# Czujnik_wiat_owodowy_schemat_elektryczny.net
KiCad netlist of a schematic drawn in Altium Designer
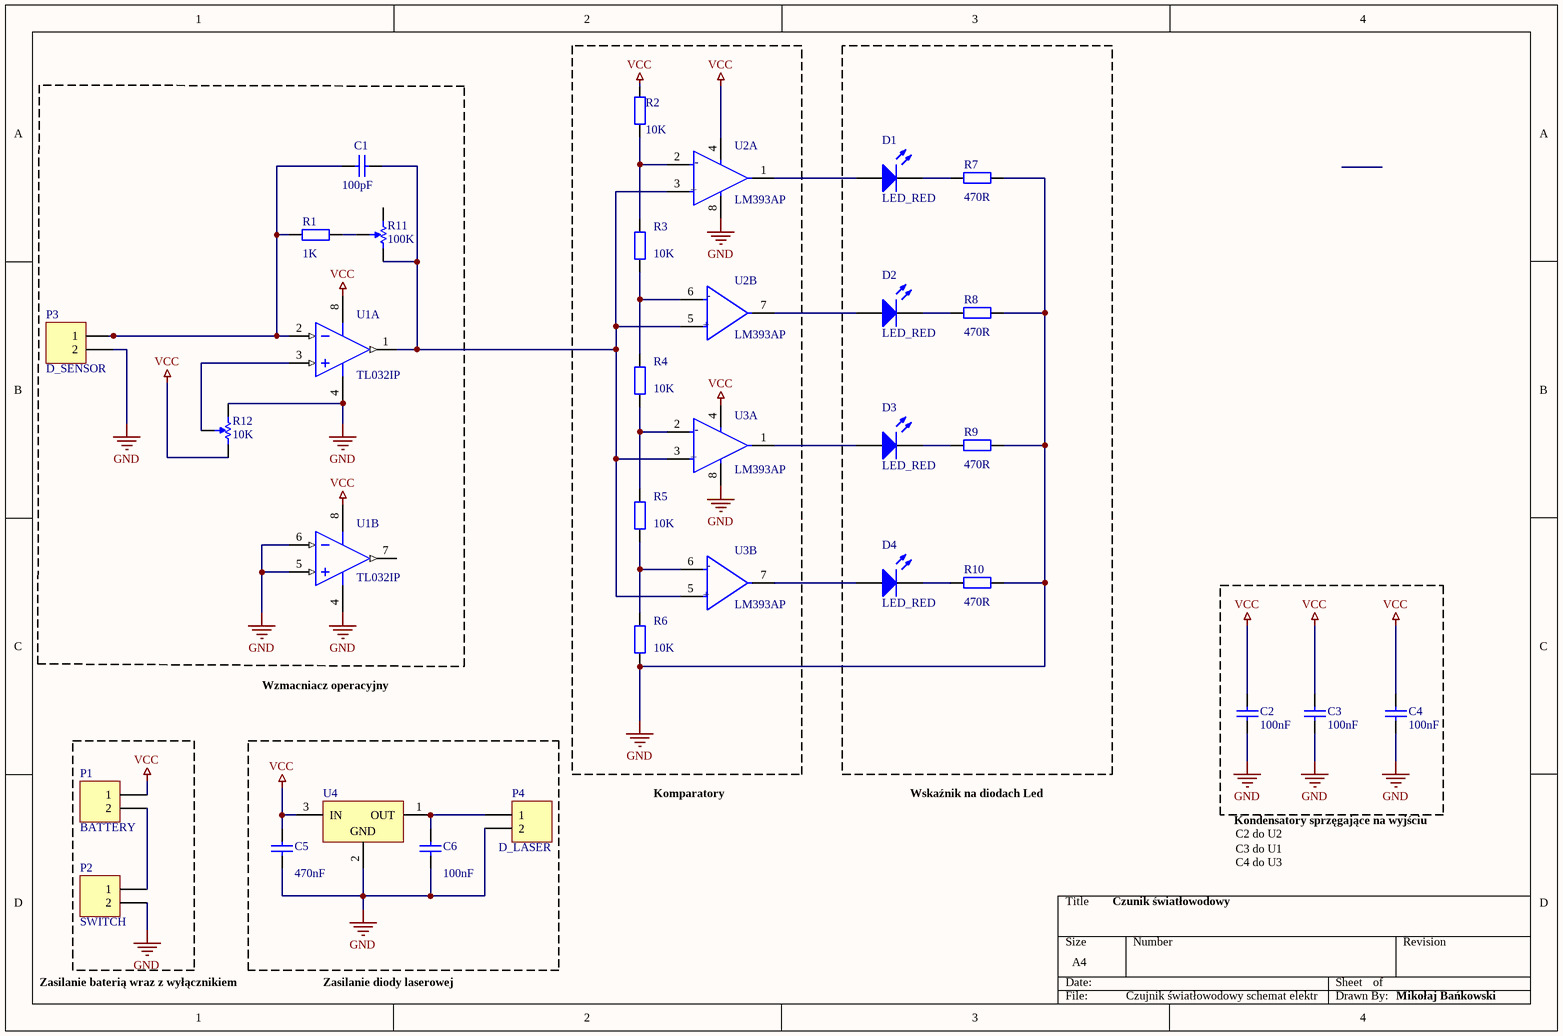
[diagram p0: Czujnik światłowodowy schemat elektryczny.SchDoc]

(export (version "E")
  (design (tool "Eeschema 10.0.6"))
  (components
    (comp (ref "C1")
      (value "100pF")
      (footprint "RAD-0.3")
      (description "Capacitor")
      (fields (field (name "Comment") "Cap") (field (name "PUBLISHER") "Altium Limited"))
      (libsource (lib "Miscellaneous Devices") (part "Cap"))
    )
    (comp (ref "C2")
      (value "100nF")
      (footprint "RAD-0.3")
      (description "Capacitor")
      (fields (field (name "Comment") "Cap") (field (name "PUBLISHER") "Altium Limited"))
      (libsource (lib "Miscellaneous Devices") (part "Cap"))
    )
    (comp (ref "C3")
      (value "100nF")
      (footprint "RAD-0.3")
      (description "Capacitor")
      (fields (field (name "Comment") "Cap") (field (name "PUBLISHER") "Altium Limited"))
      (libsource (lib "Miscellaneous Devices") (part "Cap"))
    )
    (comp (ref "C4")
      (value "100nF")
      (footprint "RAD-0.3")
      (description "Capacitor")
      (fields (field (name "Comment") "Cap") (field (name "PUBLISHER") "Altium Limited"))
      (libsource (lib "Miscellaneous Devices") (part "Cap"))
    )
    (comp (ref "C5")
      (value "470nF")
      (footprint "RAD-0.3")
      (description "Capacitor")
      (fields (field (name "Comment") "Cap") (field (name "PUBLISHER") "Altium Limited"))
      (libsource (lib "Miscellaneous Devices") (part "Cap"))
    )
    (comp (ref "C6")
      (value "100nF")
      (footprint "RAD-0.3")
      (description "Capacitor")
      (fields (field (name "Comment") "Cap") (field (name "PUBLISHER") "Altium Limited"))
      (libsource (lib "Miscellaneous Devices") (part "Cap"))
    )
    (comp (ref "D1")
      (value "LED_RED")
      (footprint "LED-1")
      (description "Typical RED GaAs LED")
      (fields (field (name "PUBLISHER") "Altium Limited"))
      (libsource (lib "Miscellaneous Devices") (part "LED1"))
    )
    (comp (ref "D2")
      (value "LED_RED")
      (footprint "LED-1")
      (description "Typical RED GaAs LED")
      (fields (field (name "PUBLISHER") "Altium Limited"))
      (libsource (lib "Miscellaneous Devices") (part "LED1"))
    )
    (comp (ref "D3")
      (value "LED_RED")
      (footprint "LED-1")
      (description "Typical RED GaAs LED")
      (fields (field (name "PUBLISHER") "Altium Limited"))
      (libsource (lib "Miscellaneous Devices") (part "LED1"))
    )
    (comp (ref "D4")
      (value "LED_RED")
      (footprint "LED-1")
      (description "Typical RED GaAs LED")
      (fields (field (name "PUBLISHER") "Altium Limited"))
      (libsource (lib "Miscellaneous Devices") (part "LED1"))
    )
    (comp (ref "P1")
      (value "BATTERY")
      (footprint "HDR1X2")
      (description "Header, 2-Pin")
      (fields (field (name "PUBLISHER") "Altium Limited"))
      (libsource (lib "Miscellaneous Connectors") (part "Header 2"))
    )
    (comp (ref "P2")
      (value "SWITCH")
      (footprint "HDR1X2")
      (description "Header, 2-Pin")
      (fields (field (name "PUBLISHER") "Altium Limited"))
      (libsource (lib "Miscellaneous Connectors") (part "Header 2"))
    )
    (comp (ref "P3")
      (value "D_SENSOR")
      (footprint "HDR1X2")
      (description "Header, 2-Pin")
      (fields (field (name "PUBLISHER") "Altium Limited"))
      (libsource (lib "Miscellaneous Connectors") (part "Header 2"))
    )
    (comp (ref "P4")
      (value "D_LASER")
      (footprint "HDR1X2")
      (description "Header, 2-Pin")
      (fields (field (name "PUBLISHER") "Altium Limited"))
      (libsource (lib "") (part "Header 2_1"))
    )
    (comp (ref "R1")
      (value "1K")
      (footprint "AXIAL-0.4")
      (description "Resistor")
      (fields (field (name "Comment") "Res2") (field (name "PUBLISHER") "Altium Limited"))
      (libsource (lib "") (part "Res2_1"))
    )
    (comp (ref "R2")
      (value "10K")
      (footprint "AXIAL-0.4")
      (description "Resistor")
      (fields (field (name "Comment") "Res2") (field (name "PUBLISHER") "Altium Limited"))
      (libsource (lib "Miscellaneous Devices") (part "Res2"))
    )
    (comp (ref "R3")
      (value "10K")
      (footprint "AXIAL-0.4")
      (description "Resistor")
      (fields (field (name "Comment") "Res2") (field (name "PUBLISHER") "Altium Limited"))
      (libsource (lib "Miscellaneous Devices") (part "Res2"))
    )
    (comp (ref "R4")
      (value "10K")
      (footprint "AXIAL-0.4")
      (description "Resistor")
      (fields (field (name "Comment") "Res2") (field (name "PUBLISHER") "Altium Limited"))
      (libsource (lib "Miscellaneous Devices") (part "Res2"))
    )
    (comp (ref "R5")
      (value "10K")
      (footprint "AXIAL-0.4")
      (description "Resistor")
      (fields (field (name "Comment") "Res2") (field (name "PUBLISHER") "Altium Limited"))
      (libsource (lib "Miscellaneous Devices") (part "Res2"))
    )
    (comp (ref "R6")
      (value "10K")
      (footprint "AXIAL-0.4")
      (description "Resistor")
      (fields (field (name "Comment") "Res2") (field (name "PUBLISHER") "Altium Limited"))
      (libsource (lib "Miscellaneous Devices") (part "Res2"))
    )
    (comp (ref "R7")
      (value "470R")
      (footprint "AXIAL-0.4")
      (description "Resistor")
      (fields (field (name "Comment") "Res2") (field (name "PUBLISHER") "Altium Limited"))
      (libsource (lib "") (part "Res2_1"))
    )
    (comp (ref "R8")
      (value "470R")
      (footprint "AXIAL-0.4")
      (description "Resistor")
      (fields (field (name "Comment") "Res2") (field (name "PUBLISHER") "Altium Limited"))
      (libsource (lib "") (part "Res2_1"))
    )
    (comp (ref "R9")
      (value "470R")
      (footprint "AXIAL-0.4")
      (description "Resistor")
      (fields (field (name "Comment") "Res2") (field (name "PUBLISHER") "Altium Limited"))
      (libsource (lib "") (part "Res2_1"))
    )
    (comp (ref "R10")
      (value "470R")
      (footprint "AXIAL-0.4")
      (description "Resistor")
      (fields (field (name "Comment") "Res2") (field (name "PUBLISHER") "Altium Limited"))
      (libsource (lib "") (part "Res2_1"))
    )
    (comp (ref "R11")
      (value "100K")
      (footprint "BOUR-3386P")
      (fields (field (name "TOLERANCE") "10%") (field (name "MANUFACTURER") "Bourns"))
      (libsource (lib "Altium Content Vault") (part "RES-ADJ-3_A"))
    )
    (comp (ref "R12")
      (value "10K")
      (footprint "BOUR-3386P")
      (fields (field (name "TOLERANCE") "10%") (field (name "MANUFACTURER") "Bourns"))
      (libsource (lib "Altium Content Vault") (part "RES-ADJ-3_A"))
    )
    (comp (ref "U1")
      (value "TL032IP")
      (footprint "P0008A")
      (fields (field (name "MANUFACTURER") "Texas Instruments"))
      (libsource (lib "Altium Content Vault") (part "TI-AMP-D6-2-8_D"))
    )
    (comp (ref "U2")
      (value "LM393AP")
      (footprint "FP-P0008A-MFG")
      (description "IC DUAL DIFF COMPARATOR 8-DIP")
      (libsource (lib "Altium Content Vault") (part "28ffe1f6a599f08a8494cd30af5fdb3"))
    )
    (comp (ref "U3")
      (value "LM393AP")
      (footprint "FP-P0008A-MFG")
      (description "IC DUAL DIFF COMPARATOR 8-DIP")
      (libsource (lib "Altium Content Vault") (part "28ffe1f6a599f08a8494cd30af5fdb3"))
    )
    (comp (ref "U4")
      (value "LM78L05ACZ/NOPB")
      (footprint "LP0003A")
      (description "3-Terminal Positive Regulator, 5 Vout, 3-pin TO-92, Pb-Free")
      (fields (field (name "MANUFACTURER") "Texas Instruments"))
      (libsource (lib "Altium Content Vault") (part "PM-REG-LM78L05-SIL3"))
    )
  )
  (nets
    (net (code "1") (name "GND") (class "Default")
      (node (ref "C2") (pin "2") (pinfunction "2_2") (pintype "passive"))
      (node (ref "C3") (pin "2") (pinfunction "2_2") (pintype "passive"))
      (node (ref "C4") (pin "2") (pinfunction "2_2") (pintype "passive"))
      (node (ref "C5") (pin "2") (pinfunction "2_2") (pintype "passive"))
      (node (ref "C6") (pin "2") (pinfunction "2_2") (pintype "passive"))
      (node (ref "P2") (pin "2") (pinfunction "2_2") (pintype "passive"))
      (node (ref "P3") (pin "2") (pinfunction "2_2") (pintype "passive"))
      (node (ref "P4") (pin "2") (pinfunction "2_2") (pintype "passive"))
      (node (ref "R10") (pin "2") (pinfunction "2_2") (pintype "passive"))
      (node (ref "R12") (pin "1") (pinfunction "1_1") (pintype "passive"))
      (node (ref "R6") (pin "1") (pinfunction "1_1") (pintype "passive"))
      (node (ref "R7") (pin "2") (pinfunction "2_2") (pintype "passive"))
      (node (ref "R8") (pin "2") (pinfunction "2_2") (pintype "passive"))
      (node (ref "R9") (pin "2") (pinfunction "2_2") (pintype "passive"))
      (node (ref "U1") (pin "4") (pinfunction "VCC-_4") (pintype "power_in"))
      (node (ref "U1") (pin "5") (pinfunction "IN2+_5") (pintype "input"))
      (node (ref "U1") (pin "6") (pinfunction "IN2-_6") (pintype "input"))
      (node (ref "U2") (pin "8") (pinfunction "VCC_8") (pintype "power_in"))
      (node (ref "U3") (pin "8") (pinfunction "VCC_8") (pintype "power_in"))
      (node (ref "U4") (pin "2") (pinfunction "GND_2") (pintype "power_in"))
    )
    (net (code "2") (name "Net-(D1-A)") (class "Default")
      (node (ref "D1") (pin "1") (pinfunction "A_1") (pintype "passive"))
      (node (ref "U2") (pin "1") (pinfunction "1OUT_1") (pintype "passive"))
    )
    (net (code "3") (name "Net-(D1-K)") (class "Default")
      (node (ref "D1") (pin "2") (pinfunction "K_2") (pintype "passive"))
      (node (ref "R7") (pin "1") (pinfunction "1_1") (pintype "passive"))
    )
    (net (code "4") (name "Net-(D2-A)") (class "Default")
      (node (ref "D2") (pin "1") (pinfunction "A_1") (pintype "passive"))
      (node (ref "U2") (pin "7") (pinfunction "2OUT_7") (pintype "passive"))
    )
    (net (code "5") (name "Net-(D2-K)") (class "Default")
      (node (ref "D2") (pin "2") (pinfunction "K_2") (pintype "passive"))
      (node (ref "R8") (pin "1") (pinfunction "1_1") (pintype "passive"))
    )
    (net (code "6") (name "Net-(D3-A)") (class "Default")
      (node (ref "D3") (pin "1") (pinfunction "A_1") (pintype "passive"))
      (node (ref "U3") (pin "1") (pinfunction "1OUT_1") (pintype "passive"))
    )
    (net (code "7") (name "Net-(D3-K)") (class "Default")
      (node (ref "D3") (pin "2") (pinfunction "K_2") (pintype "passive"))
      (node (ref "R9") (pin "1") (pinfunction "1_1") (pintype "passive"))
    )
    (net (code "8") (name "Net-(D4-A)") (class "Default")
      (node (ref "D4") (pin "1") (pinfunction "A_1") (pintype "passive"))
      (node (ref "U3") (pin "7") (pinfunction "2OUT_7") (pintype "passive"))
    )
    (net (code "9") (name "Net-(D4-K)") (class "Default")
      (node (ref "D4") (pin "2") (pinfunction "K_2") (pintype "passive"))
      (node (ref "R10") (pin "1") (pinfunction "1_1") (pintype "passive"))
    )
    (net (code "10") (name "Net-(P1-Pad2)") (class "Default")
      (node (ref "P1") (pin "2") (pinfunction "2_2") (pintype "passive"))
      (node (ref "P2") (pin "1") (pinfunction "1_1") (pintype "passive"))
    )
    (net (code "11") (name "Net-(R1-Pad2)") (class "Default")
      (node (ref "R1") (pin "2") (pinfunction "2_2") (pintype "passive"))
      (node (ref "R11") (pin "2") (pinfunction "2_2") (pintype "passive"))
    )
    (net (code "12") (name "Net-(U1A-IN1+)") (class "Default")
      (node (ref "R12") (pin "2") (pinfunction "2_2") (pintype "passive"))
      (node (ref "U1") (pin "3") (pinfunction "IN1+_3") (pintype "input"))
    )
    (net (code "13") (name "Net-(U1A-IN1-)") (class "Default")
      (node (ref "C1") (pin "1") (pinfunction "1_1") (pintype "passive"))
      (node (ref "P3") (pin "1") (pinfunction "1_1") (pintype "passive"))
      (node (ref "R1") (pin "1") (pinfunction "1_1") (pintype "passive"))
      (node (ref "U1") (pin "2") (pinfunction "IN1-_2") (pintype "input"))
    )
    (net (code "14") (name "Net-(U1A-OUT1)") (class "Default")
      (node (ref "C1") (pin "2") (pinfunction "2_2") (pintype "passive"))
      (node (ref "R11") (pin "3") (pinfunction "3_3") (pintype "passive"))
      (node (ref "U1") (pin "1") (pinfunction "OUT1_1") (pintype "output"))
      (node (ref "U2") (pin "3") (pinfunction "1IN+_3") (pintype "tri_state"))
      (node (ref "U2") (pin "5") (pinfunction "2IN+_5") (pintype "tri_state"))
      (node (ref "U3") (pin "3") (pinfunction "1IN+_3") (pintype "tri_state"))
      (node (ref "U3") (pin "5") (pinfunction "2IN+_5") (pintype "tri_state"))
    )
    (net (code "15") (name "Net-(U2A-1IN-)") (class "Default")
      (node (ref "R2") (pin "1") (pinfunction "1_1") (pintype "passive"))
      (node (ref "R3") (pin "2") (pinfunction "2_2") (pintype "passive"))
      (node (ref "U2") (pin "2") (pinfunction "1IN-_2") (pintype "tri_state"))
    )
    (net (code "16") (name "Net-(U2B-2IN-)") (class "Default")
      (node (ref "R3") (pin "1") (pinfunction "1_1") (pintype "passive"))
      (node (ref "R4") (pin "2") (pinfunction "2_2") (pintype "passive"))
      (node (ref "U2") (pin "6") (pinfunction "2IN-_6") (pintype "tri_state"))
    )
    (net (code "17") (name "Net-(U3A-1IN-)") (class "Default")
      (node (ref "R4") (pin "1") (pinfunction "1_1") (pintype "passive"))
      (node (ref "R5") (pin "2") (pinfunction "2_2") (pintype "passive"))
      (node (ref "U3") (pin "2") (pinfunction "1IN-_2") (pintype "tri_state"))
    )
    (net (code "18") (name "Net-(U3B-2IN-)") (class "Default")
      (node (ref "R5") (pin "1") (pinfunction "1_1") (pintype "passive"))
      (node (ref "R6") (pin "2") (pinfunction "2_2") (pintype "passive"))
      (node (ref "U3") (pin "6") (pinfunction "2IN-_6") (pintype "tri_state"))
    )
    (net (code "19") (name "Net-(U4-OUT)") (class "Default")
      (node (ref "C6") (pin "1") (pinfunction "1_1") (pintype "passive"))
      (node (ref "P4") (pin "1") (pinfunction "1_1") (pintype "passive"))
      (node (ref "U4") (pin "1") (pinfunction "OUT_1") (pintype "power_in"))
    )
    (net (code "20") (name "VCC") (class "Default")
      (node (ref "C2") (pin "1") (pinfunction "1_1") (pintype "passive"))
      (node (ref "C3") (pin "1") (pinfunction "1_1") (pintype "passive"))
      (node (ref "C4") (pin "1") (pinfunction "1_1") (pintype "passive"))
      (node (ref "C5") (pin "1") (pinfunction "1_1") (pintype "passive"))
      (node (ref "P1") (pin "1") (pinfunction "1_1") (pintype "passive"))
      (node (ref "R12") (pin "3") (pinfunction "3_3") (pintype "passive"))
      (node (ref "R2") (pin "2") (pinfunction "2_2") (pintype "passive"))
      (node (ref "U1") (pin "8") (pinfunction "VCC+_8") (pintype "power_in"))
      (node (ref "U2") (pin "4") (pinfunction "GND_4") (pintype "power_in"))
      (node (ref "U3") (pin "4") (pinfunction "GND_4") (pintype "power_in"))
      (node (ref "U4") (pin "3") (pinfunction "IN_3") (pintype "power_in"))
    )
    (net (code "21") (name "unconnected-(R11-Pad1)") (class "Default")
      (node (ref "R11") (pin "1") (pinfunction "1_1") (pintype "passive"))
    )
    (net (code "22") (name "unconnected-(U1B-OUT2-Pad7)") (class "Default")
      (node (ref "U1") (pin "7") (pinfunction "OUT2_7") (pintype "output"))
    )
  )
)
